# contactor_connectors.net
KiCad netlist of a schematic drawn in Altium Designer
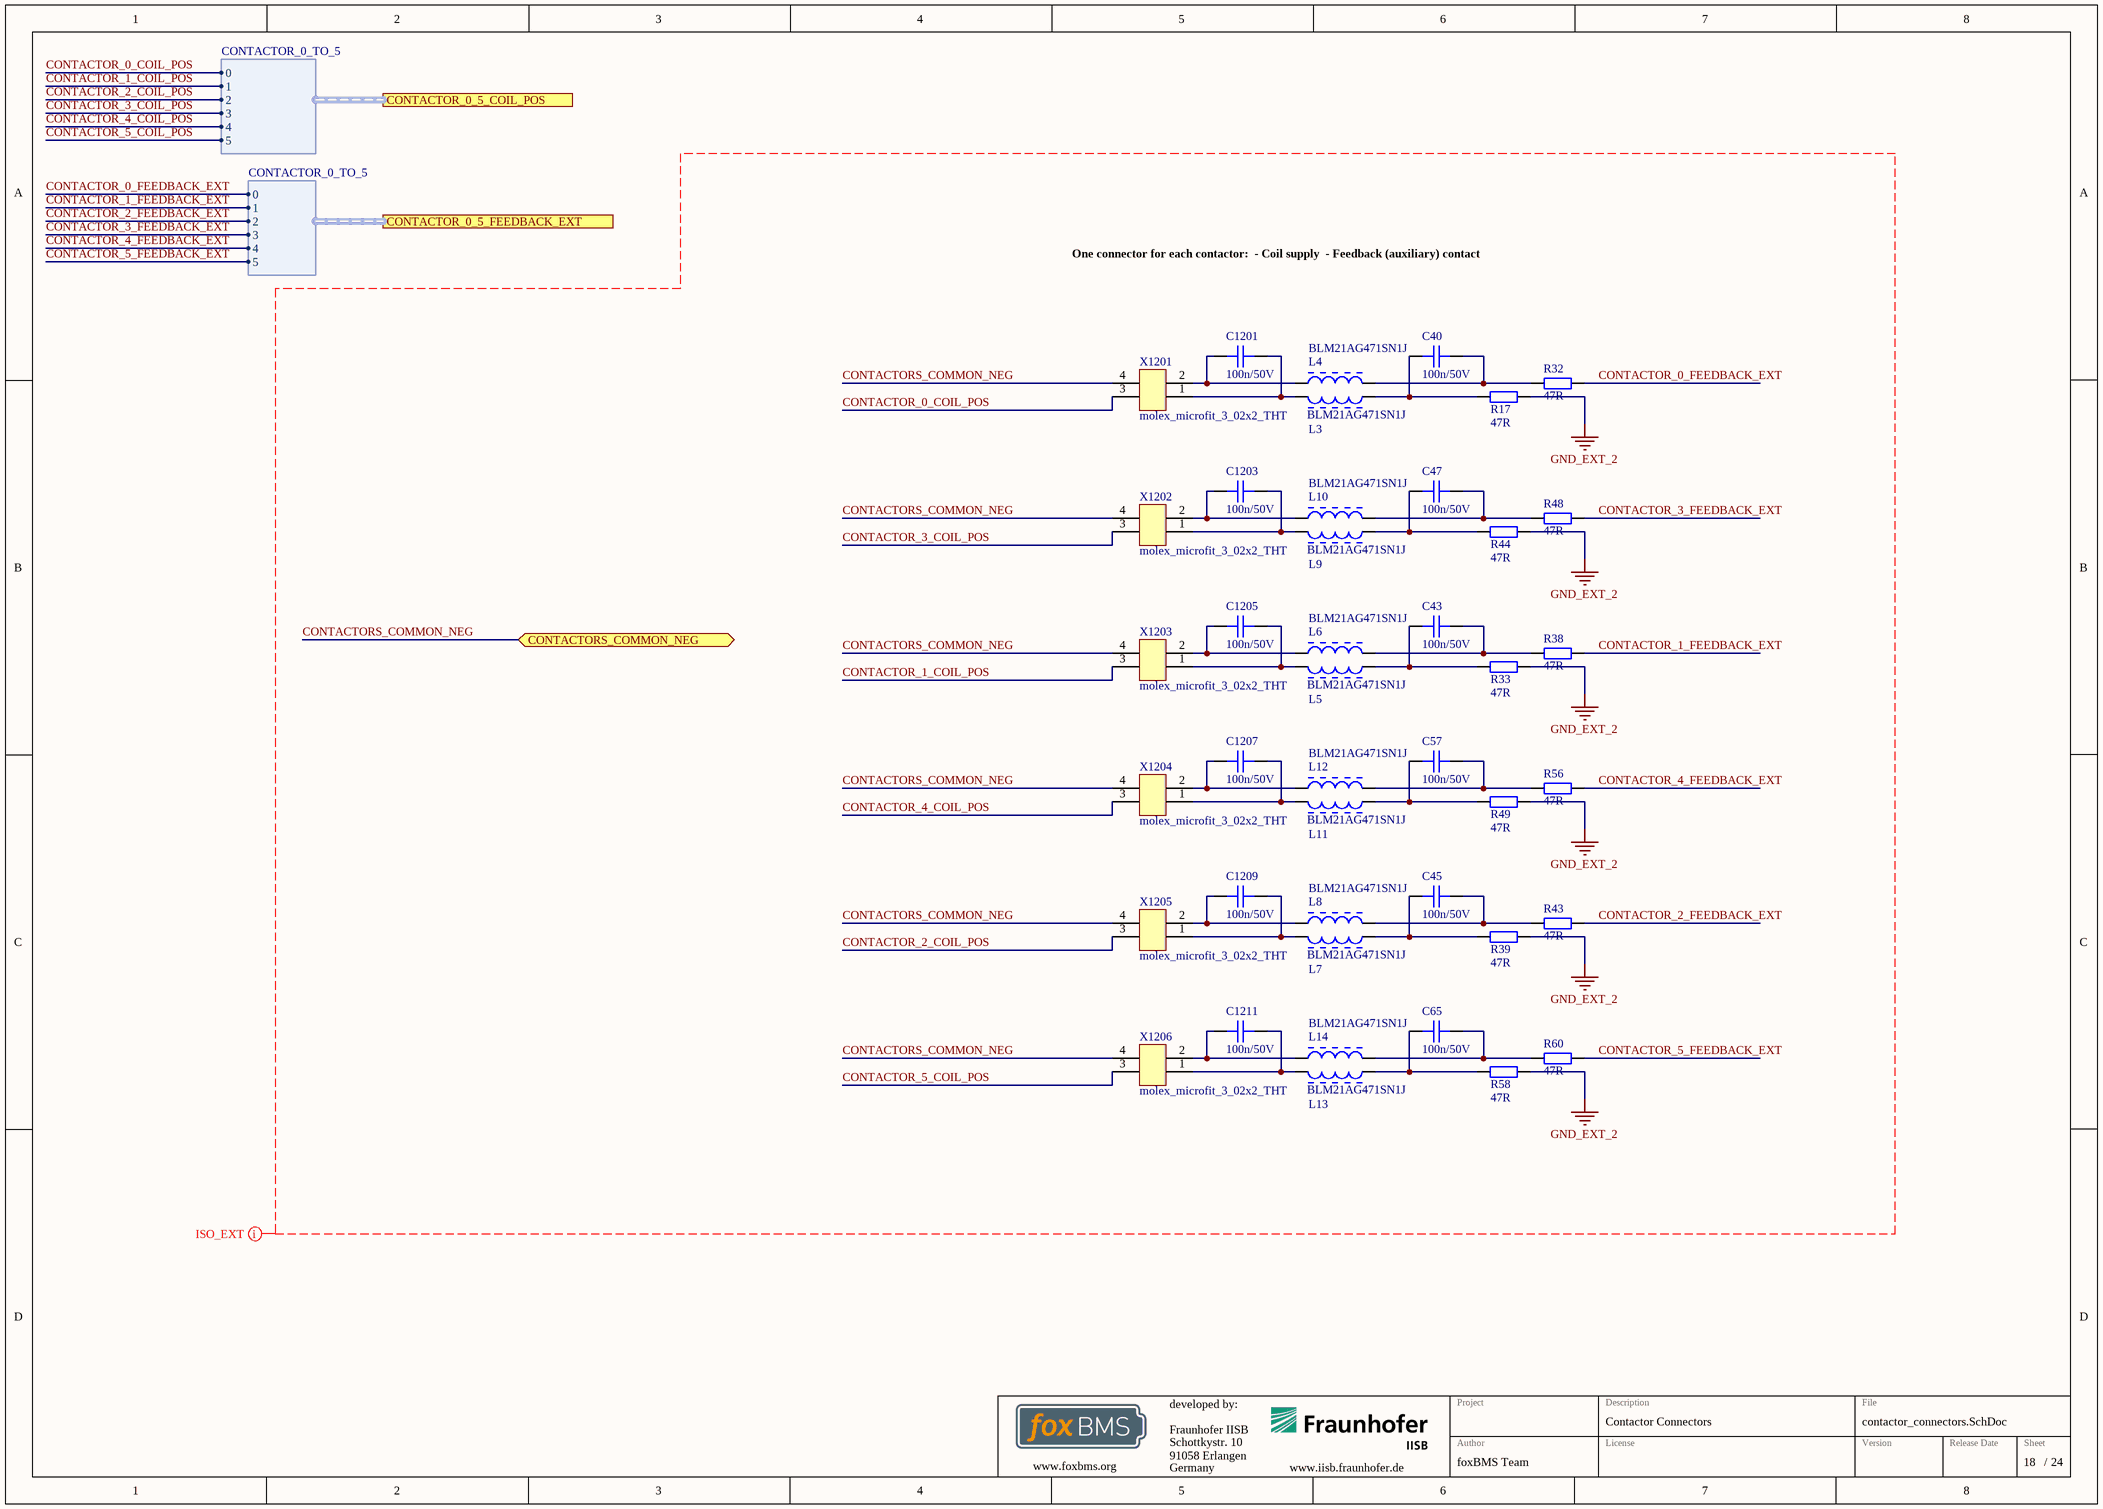
[diagram p0: contactor_connectors.SchDoc]

(export (version "E")
  (design (tool "Eeschema 10.0.6"))
  (components
    (comp (ref "C40")
      (value "100n/50V")
      (footprint "0603C")
      (description "MLCC")
      (fields (field (name "PART NUMBER") "gen_C_ceramic_100n_50V_X7R_0603"))
      (libsource (lib "OE750") (part "C"))
    )
    (comp (ref "C43")
      (value "100n/50V")
      (footprint "0603C")
      (description "MLCC")
      (fields (field (name "PART NUMBER") "gen_C_ceramic_100n_50V_X7R_0603"))
      (libsource (lib "OE750") (part "C"))
    )
    (comp (ref "C45")
      (value "100n/50V")
      (footprint "0603C")
      (description "MLCC")
      (fields (field (name "PART NUMBER") "gen_C_ceramic_100n_50V_X7R_0603"))
      (libsource (lib "OE750") (part "C"))
    )
    (comp (ref "C47")
      (value "100n/50V")
      (footprint "0603C")
      (description "MLCC")
      (fields (field (name "PART NUMBER") "gen_C_ceramic_100n_50V_X7R_0603"))
      (libsource (lib "OE750") (part "C"))
    )
    (comp (ref "C57")
      (value "100n/50V")
      (footprint "0603C")
      (description "MLCC")
      (fields (field (name "PART NUMBER") "gen_C_ceramic_100n_50V_X7R_0603"))
      (libsource (lib "OE750") (part "C"))
    )
    (comp (ref "C65")
      (value "100n/50V")
      (footprint "0603C")
      (description "MLCC")
      (fields (field (name "PART NUMBER") "gen_C_ceramic_100n_50V_X7R_0603"))
      (libsource (lib "OE750") (part "C"))
    )
    (comp (ref "C1201")
      (value "100n/50V")
      (footprint "0603C")
      (description "MLCC")
      (fields (field (name "PART NUMBER") "gen_C_ceramic_100n_50V_X7R_0603"))
      (libsource (lib "OE750") (part "C"))
    )
    (comp (ref "C1203")
      (value "100n/50V")
      (footprint "0603C")
      (description "MLCC")
      (fields (field (name "PART NUMBER") "gen_C_ceramic_100n_50V_X7R_0603"))
      (libsource (lib "OE750") (part "C"))
    )
    (comp (ref "C1205")
      (value "100n/50V")
      (footprint "0603C")
      (description "MLCC")
      (fields (field (name "PART NUMBER") "gen_C_ceramic_100n_50V_X7R_0603"))
      (libsource (lib "OE750") (part "C"))
    )
    (comp (ref "C1207")
      (value "100n/50V")
      (footprint "0603C")
      (description "MLCC")
      (fields (field (name "PART NUMBER") "gen_C_ceramic_100n_50V_X7R_0603"))
      (libsource (lib "OE750") (part "C"))
    )
    (comp (ref "C1209")
      (value "100n/50V")
      (footprint "0603C")
      (description "MLCC")
      (fields (field (name "PART NUMBER") "gen_C_ceramic_100n_50V_X7R_0603"))
      (libsource (lib "OE750") (part "C"))
    )
    (comp (ref "C1211")
      (value "100n/50V")
      (footprint "0603C")
      (description "MLCC")
      (fields (field (name "PART NUMBER") "gen_C_ceramic_100n_50V_X7R_0603"))
      (libsource (lib "OE750") (part "C"))
    )
    (comp (ref "L3")
      (value "BLM21AG471SN1J")
      (footprint "MURA-BLM21-H1-CHIP-2_V")
      (fields (field (name "MANUFACTURER") "Murata"))
      (libsource (lib "Altium Content Vault") (part "MURA-FB-2"))
    )
    (comp (ref "L4")
      (value "BLM21AG471SN1J")
      (footprint "MURA-BLM21-H1-CHIP-2_V")
      (fields (field (name "MANUFACTURER") "Murata"))
      (libsource (lib "") (part "MURA-FB-2_1"))
    )
    (comp (ref "L5")
      (value "BLM21AG471SN1J")
      (footprint "MURA-BLM21-H1-CHIP-2_V")
      (fields (field (name "MANUFACTURER") "Murata"))
      (libsource (lib "Altium Content Vault") (part "MURA-FB-2"))
    )
    (comp (ref "L6")
      (value "BLM21AG471SN1J")
      (footprint "MURA-BLM21-H1-CHIP-2_V")
      (fields (field (name "MANUFACTURER") "Murata"))
      (libsource (lib "") (part "MURA-FB-2_1"))
    )
    (comp (ref "L7")
      (value "BLM21AG471SN1J")
      (footprint "MURA-BLM21-H1-CHIP-2_V")
      (fields (field (name "MANUFACTURER") "Murata"))
      (libsource (lib "Altium Content Vault") (part "MURA-FB-2"))
    )
    (comp (ref "L8")
      (value "BLM21AG471SN1J")
      (footprint "MURA-BLM21-H1-CHIP-2_V")
      (fields (field (name "MANUFACTURER") "Murata"))
      (libsource (lib "") (part "MURA-FB-2_1"))
    )
    (comp (ref "L9")
      (value "BLM21AG471SN1J")
      (footprint "MURA-BLM21-H1-CHIP-2_V")
      (fields (field (name "MANUFACTURER") "Murata"))
      (libsource (lib "Altium Content Vault") (part "MURA-FB-2"))
    )
    (comp (ref "L10")
      (value "BLM21AG471SN1J")
      (footprint "MURA-BLM21-H1-CHIP-2_V")
      (fields (field (name "MANUFACTURER") "Murata"))
      (libsource (lib "") (part "MURA-FB-2_1"))
    )
    (comp (ref "L11")
      (value "BLM21AG471SN1J")
      (footprint "MURA-BLM21-H1-CHIP-2_V")
      (fields (field (name "MANUFACTURER") "Murata"))
      (libsource (lib "Altium Content Vault") (part "MURA-FB-2"))
    )
    (comp (ref "L12")
      (value "BLM21AG471SN1J")
      (footprint "MURA-BLM21-H1-CHIP-2_V")
      (fields (field (name "MANUFACTURER") "Murata"))
      (libsource (lib "") (part "MURA-FB-2_1"))
    )
    (comp (ref "L13")
      (value "BLM21AG471SN1J")
      (footprint "MURA-BLM21-H1-CHIP-2_V")
      (fields (field (name "MANUFACTURER") "Murata"))
      (libsource (lib "Altium Content Vault") (part "MURA-FB-2"))
    )
    (comp (ref "L14")
      (value "BLM21AG471SN1J")
      (footprint "MURA-BLM21-H1-CHIP-2_V")
      (fields (field (name "MANUFACTURER") "Murata"))
      (libsource (lib "") (part "MURA-FB-2_1"))
    )
    (comp (ref "R17")
      (value "47R")
      (footprint "0603R")
      (description "SMD Resistor 47R 0603")
      (fields (field (name "PART NUMBER") "gen_R_47R_0603") (field (name "TOLERANCE") "1%"))
      (libsource (lib "OE750") (part "R"))
    )
    (comp (ref "R32")
      (value "47R")
      (footprint "0603R")
      (description "SMD Resistor 47R 0603")
      (fields (field (name "PART NUMBER") "gen_R_47R_0603") (field (name "TOLERANCE") "1%"))
      (libsource (lib "OE750") (part "R"))
    )
    (comp (ref "R33")
      (value "47R")
      (footprint "0603R")
      (description "SMD Resistor 47R 0603")
      (fields (field (name "PART NUMBER") "gen_R_47R_0603") (field (name "TOLERANCE") "1%"))
      (libsource (lib "OE750") (part "R"))
    )
    (comp (ref "R38")
      (value "47R")
      (footprint "0603R")
      (description "SMD Resistor 47R 0603")
      (fields (field (name "PART NUMBER") "gen_R_47R_0603") (field (name "TOLERANCE") "1%"))
      (libsource (lib "OE750") (part "R"))
    )
    (comp (ref "R39")
      (value "47R")
      (footprint "0603R")
      (description "SMD Resistor 47R 0603")
      (fields (field (name "PART NUMBER") "gen_R_47R_0603") (field (name "TOLERANCE") "1%"))
      (libsource (lib "OE750") (part "R"))
    )
    (comp (ref "R43")
      (value "47R")
      (footprint "0603R")
      (description "SMD Resistor 47R 0603")
      (fields (field (name "PART NUMBER") "gen_R_47R_0603") (field (name "TOLERANCE") "1%"))
      (libsource (lib "OE750") (part "R"))
    )
    (comp (ref "R44")
      (value "47R")
      (footprint "0603R")
      (description "SMD Resistor 47R 0603")
      (fields (field (name "PART NUMBER") "gen_R_47R_0603") (field (name "TOLERANCE") "1%"))
      (libsource (lib "OE750") (part "R"))
    )
    (comp (ref "R48")
      (value "47R")
      (footprint "0603R")
      (description "SMD Resistor 47R 0603")
      (fields (field (name "PART NUMBER") "gen_R_47R_0603") (field (name "TOLERANCE") "1%"))
      (libsource (lib "OE750") (part "R"))
    )
    (comp (ref "R49")
      (value "47R")
      (footprint "0603R")
      (description "SMD Resistor 47R 0603")
      (fields (field (name "PART NUMBER") "gen_R_47R_0603") (field (name "TOLERANCE") "1%"))
      (libsource (lib "OE750") (part "R"))
    )
    (comp (ref "R56")
      (value "47R")
      (footprint "0603R")
      (description "SMD Resistor 47R 0603")
      (fields (field (name "PART NUMBER") "gen_R_47R_0603") (field (name "TOLERANCE") "1%"))
      (libsource (lib "OE750") (part "R"))
    )
    (comp (ref "R58")
      (value "47R")
      (footprint "0603R")
      (description "SMD Resistor 47R 0603")
      (fields (field (name "PART NUMBER") "gen_R_47R_0603") (field (name "TOLERANCE") "1%"))
      (libsource (lib "OE750") (part "R"))
    )
    (comp (ref "R60")
      (value "47R")
      (footprint "0603R")
      (description "SMD Resistor 47R 0603")
      (fields (field (name "PART NUMBER") "gen_R_47R_0603") (field (name "TOLERANCE") "1%"))
      (libsource (lib "OE750") (part "R"))
    )
    (comp (ref "X1201")
      (value "molex_microfit_3_02x2_THT")
      (footprint "43045-0421")
      (fields (field (name "MANUFACTURER") "Molex"))
      (libsource (lib "OE750") (part "X2x2"))
    )
    (comp (ref "X1202")
      (value "molex_microfit_3_02x2_THT")
      (footprint "43045-0421")
      (fields (field (name "MANUFACTURER") "Molex"))
      (libsource (lib "OE750") (part "X2x2"))
    )
    (comp (ref "X1203")
      (value "molex_microfit_3_02x2_THT")
      (footprint "43045-0421")
      (fields (field (name "MANUFACTURER") "Molex"))
      (libsource (lib "OE750") (part "X2x2"))
    )
    (comp (ref "X1204")
      (value "molex_microfit_3_02x2_THT")
      (footprint "43045-0421")
      (fields (field (name "MANUFACTURER") "Molex"))
      (libsource (lib "OE750") (part "X2x2"))
    )
    (comp (ref "X1205")
      (value "molex_microfit_3_02x2_THT")
      (footprint "43045-0421")
      (fields (field (name "MANUFACTURER") "Molex"))
      (libsource (lib "OE750") (part "X2x2"))
    )
    (comp (ref "X1206")
      (value "molex_microfit_3_02x2_THT")
      (footprint "43045-0421")
      (fields (field (name "MANUFACTURER") "Molex"))
      (libsource (lib "OE750") (part "X2x2"))
    )
  )
  (nets
    (net (code "2") (name "/CONTACTORS_COMMON_NEG") (class "Default")
      (node (ref "X1201") (pin "4") (pintype "passive"))
      (node (ref "X1202") (pin "4") (pintype "passive"))
      (node (ref "X1203") (pin "4") (pintype "passive"))
      (node (ref "X1204") (pin "4") (pintype "passive"))
      (node (ref "X1205") (pin "4") (pintype "passive"))
      (node (ref "X1206") (pin "4") (pintype "passive"))
    )
    (net (code "3") (name "/CONTACTOR_0_COIL_POS") (class "Default")
      (node (ref "X1201") (pin "3") (pintype "passive"))
    )
    (net (code "4") (name "/CONTACTOR_0_FEEDBACK_EXT") (class "Default")
      (node (ref "R32") (pin "1") (pinfunction "1_1") (pintype "passive"))
    )
    (net (code "5") (name "/CONTACTOR_1_COIL_POS") (class "Default")
      (node (ref "X1203") (pin "3") (pintype "passive"))
    )
    (net (code "6") (name "/CONTACTOR_1_FEEDBACK_EXT") (class "Default")
      (node (ref "R38") (pin "1") (pinfunction "1_1") (pintype "passive"))
    )
    (net (code "7") (name "/CONTACTOR_2_COIL_POS") (class "Default")
      (node (ref "X1205") (pin "3") (pintype "passive"))
    )
    (net (code "8") (name "/CONTACTOR_2_FEEDBACK_EXT") (class "Default")
      (node (ref "R43") (pin "2") (pinfunction "2_2") (pintype "passive"))
    )
    (net (code "9") (name "/CONTACTOR_3_COIL_POS") (class "Default")
      (node (ref "X1202") (pin "3") (pintype "passive"))
    )
    (net (code "10") (name "/CONTACTOR_3_FEEDBACK_EXT") (class "Default")
      (node (ref "R48") (pin "1") (pinfunction "1_1") (pintype "passive"))
    )
    (net (code "11") (name "/CONTACTOR_4_COIL_POS") (class "Default")
      (node (ref "X1204") (pin "3") (pintype "passive"))
    )
    (net (code "12") (name "/CONTACTOR_4_FEEDBACK_EXT") (class "Default")
      (node (ref "R56") (pin "2") (pinfunction "2_2") (pintype "passive"))
    )
    (net (code "13") (name "/CONTACTOR_5_COIL_POS") (class "Default")
      (node (ref "X1206") (pin "3") (pintype "passive"))
    )
    (net (code "14") (name "/CONTACTOR_5_FEEDBACK_EXT") (class "Default")
      (node (ref "R60") (pin "2") (pinfunction "2_2") (pintype "passive"))
    )
    (net (code "16") (name "GND_EXT_2") (class "Default")
      (node (ref "R17") (pin "2") (pinfunction "2_2") (pintype "passive"))
      (node (ref "R33") (pin "2") (pinfunction "2_2") (pintype "passive"))
      (node (ref "R39") (pin "2") (pinfunction "2_2") (pintype "passive"))
      (node (ref "R44") (pin "2") (pinfunction "2_2") (pintype "passive"))
      (node (ref "R49") (pin "2") (pinfunction "2_2") (pintype "passive"))
      (node (ref "R58") (pin "2") (pinfunction "2_2") (pintype "passive"))
    )
    (net (code "17") (name "Net-(C40-Pad1)") (class "Default")
      (node (ref "C40") (pin "1") (pinfunction "1_1") (pintype "passive"))
      (node (ref "L3") (pin "2") (pinfunction "2_2") (pintype "passive"))
      (node (ref "R17") (pin "1") (pinfunction "1_1") (pintype "passive"))
    )
    (net (code "18") (name "Net-(C40-Pad2)") (class "Default")
      (node (ref "C40") (pin "2") (pinfunction "2_2") (pintype "passive"))
      (node (ref "L4") (pin "2") (pinfunction "2_2") (pintype "passive"))
      (node (ref "R32") (pin "2") (pinfunction "2_2") (pintype "passive"))
    )
    (net (code "19") (name "Net-(C43-Pad1)") (class "Default")
      (node (ref "C43") (pin "1") (pinfunction "1_1") (pintype "passive"))
      (node (ref "L5") (pin "2") (pinfunction "2_2") (pintype "passive"))
      (node (ref "R33") (pin "1") (pinfunction "1_1") (pintype "passive"))
    )
    (net (code "20") (name "Net-(C43-Pad2)") (class "Default")
      (node (ref "C43") (pin "2") (pinfunction "2_2") (pintype "passive"))
      (node (ref "L6") (pin "2") (pinfunction "2_2") (pintype "passive"))
      (node (ref "R38") (pin "2") (pinfunction "2_2") (pintype "passive"))
    )
    (net (code "21") (name "Net-(C45-Pad1)") (class "Default")
      (node (ref "C45") (pin "1") (pinfunction "1_1") (pintype "passive"))
      (node (ref "L7") (pin "2") (pinfunction "2_2") (pintype "passive"))
      (node (ref "R39") (pin "1") (pinfunction "1_1") (pintype "passive"))
    )
    (net (code "22") (name "Net-(C45-Pad2)") (class "Default")
      (node (ref "C45") (pin "2") (pinfunction "2_2") (pintype "passive"))
      (node (ref "L8") (pin "2") (pinfunction "2_2") (pintype "passive"))
      (node (ref "R43") (pin "1") (pinfunction "1_1") (pintype "passive"))
    )
    (net (code "23") (name "Net-(C47-Pad1)") (class "Default")
      (node (ref "C47") (pin "1") (pinfunction "1_1") (pintype "passive"))
      (node (ref "L9") (pin "2") (pinfunction "2_2") (pintype "passive"))
      (node (ref "R44") (pin "1") (pinfunction "1_1") (pintype "passive"))
    )
    (net (code "24") (name "Net-(C47-Pad2)") (class "Default")
      (node (ref "C47") (pin "2") (pinfunction "2_2") (pintype "passive"))
      (node (ref "L10") (pin "2") (pinfunction "2_2") (pintype "passive"))
      (node (ref "R48") (pin "2") (pinfunction "2_2") (pintype "passive"))
    )
    (net (code "25") (name "Net-(C57-Pad1)") (class "Default")
      (node (ref "C57") (pin "1") (pinfunction "1_1") (pintype "passive"))
      (node (ref "L11") (pin "2") (pinfunction "2_2") (pintype "passive"))
      (node (ref "R49") (pin "1") (pinfunction "1_1") (pintype "passive"))
    )
    (net (code "26") (name "Net-(C57-Pad2)") (class "Default")
      (node (ref "C57") (pin "2") (pinfunction "2_2") (pintype "passive"))
      (node (ref "L12") (pin "2") (pinfunction "2_2") (pintype "passive"))
      (node (ref "R56") (pin "1") (pinfunction "1_1") (pintype "passive"))
    )
    (net (code "27") (name "Net-(C65-Pad1)") (class "Default")
      (node (ref "C65") (pin "1") (pinfunction "1_1") (pintype "passive"))
      (node (ref "L13") (pin "2") (pinfunction "2_2") (pintype "passive"))
      (node (ref "R58") (pin "1") (pinfunction "1_1") (pintype "passive"))
    )
    (net (code "28") (name "Net-(C65-Pad2)") (class "Default")
      (node (ref "C65") (pin "2") (pinfunction "2_2") (pintype "passive"))
      (node (ref "L14") (pin "2") (pinfunction "2_2") (pintype "passive"))
      (node (ref "R60") (pin "1") (pinfunction "1_1") (pintype "passive"))
    )
    (net (code "29") (name "Net-(C1201-Pad1)") (class "Default")
      (node (ref "C1201") (pin "1") (pinfunction "1_1") (pintype "passive"))
      (node (ref "L4") (pin "1") (pinfunction "1_1") (pintype "passive"))
      (node (ref "X1201") (pin "2") (pintype "passive"))
    )
    (net (code "30") (name "Net-(C1201-Pad2)") (class "Default")
      (node (ref "C1201") (pin "2") (pinfunction "2_2") (pintype "passive"))
      (node (ref "L3") (pin "1") (pinfunction "1_1") (pintype "passive"))
      (node (ref "X1201") (pin "1") (pintype "passive"))
    )
    (net (code "31") (name "Net-(C1203-Pad1)") (class "Default")
      (node (ref "C1203") (pin "1") (pinfunction "1_1") (pintype "passive"))
      (node (ref "L10") (pin "1") (pinfunction "1_1") (pintype "passive"))
      (node (ref "X1202") (pin "2") (pintype "passive"))
    )
    (net (code "32") (name "Net-(C1203-Pad2)") (class "Default")
      (node (ref "C1203") (pin "2") (pinfunction "2_2") (pintype "passive"))
      (node (ref "L9") (pin "1") (pinfunction "1_1") (pintype "passive"))
      (node (ref "X1202") (pin "1") (pintype "passive"))
    )
    (net (code "33") (name "Net-(C1205-Pad1)") (class "Default")
      (node (ref "C1205") (pin "1") (pinfunction "1_1") (pintype "passive"))
      (node (ref "L6") (pin "1") (pinfunction "1_1") (pintype "passive"))
      (node (ref "X1203") (pin "2") (pintype "passive"))
    )
    (net (code "34") (name "Net-(C1205-Pad2)") (class "Default")
      (node (ref "C1205") (pin "2") (pinfunction "2_2") (pintype "passive"))
      (node (ref "L5") (pin "1") (pinfunction "1_1") (pintype "passive"))
      (node (ref "X1203") (pin "1") (pintype "passive"))
    )
    (net (code "35") (name "Net-(C1207-Pad1)") (class "Default")
      (node (ref "C1207") (pin "1") (pinfunction "1_1") (pintype "passive"))
      (node (ref "L12") (pin "1") (pinfunction "1_1") (pintype "passive"))
      (node (ref "X1204") (pin "2") (pintype "passive"))
    )
    (net (code "36") (name "Net-(C1207-Pad2)") (class "Default")
      (node (ref "C1207") (pin "2") (pinfunction "2_2") (pintype "passive"))
      (node (ref "L11") (pin "1") (pinfunction "1_1") (pintype "passive"))
      (node (ref "X1204") (pin "1") (pintype "passive"))
    )
    (net (code "37") (name "Net-(C1209-Pad1)") (class "Default")
      (node (ref "C1209") (pin "1") (pinfunction "1_1") (pintype "passive"))
      (node (ref "L8") (pin "1") (pinfunction "1_1") (pintype "passive"))
      (node (ref "X1205") (pin "2") (pintype "passive"))
    )
    (net (code "38") (name "Net-(C1209-Pad2)") (class "Default")
      (node (ref "C1209") (pin "2") (pinfunction "2_2") (pintype "passive"))
      (node (ref "L7") (pin "1") (pinfunction "1_1") (pintype "passive"))
      (node (ref "X1205") (pin "1") (pintype "passive"))
    )
    (net (code "39") (name "Net-(C1211-Pad1)") (class "Default")
      (node (ref "C1211") (pin "1") (pinfunction "1_1") (pintype "passive"))
      (node (ref "L14") (pin "1") (pinfunction "1_1") (pintype "passive"))
      (node (ref "X1206") (pin "2") (pintype "passive"))
    )
    (net (code "40") (name "Net-(C1211-Pad2)") (class "Default")
      (node (ref "C1211") (pin "2") (pinfunction "2_2") (pintype "passive"))
      (node (ref "L13") (pin "1") (pinfunction "1_1") (pintype "passive"))
      (node (ref "X1206") (pin "1") (pintype "passive"))
    )
  )
)
